# EntradaSensorTemperatura.net
KiCad netlist of a schematic drawn in Altium Designer
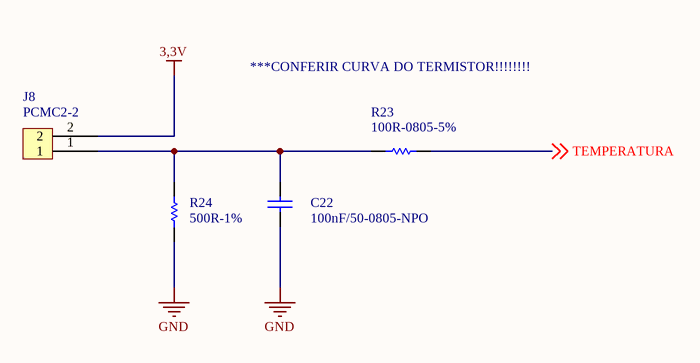
[diagram p0: EntradaSensorTemperatura.SchDoc]

(export (version "E")
  (design (tool "Eeschema 10.0.6"))
  (components
    (comp (ref "C22")
      (value "100nF/50-0805-NPO")
      (footprint "0805-REVISADO ONDA")
      (libsource (lib "AquinoLib") (part "100nF/50-0805-NPO"))
    )
    (comp (ref "J8") (value "PCMC2-2") (footprint "PCMC2-2") (libsource (lib "AquinoLib") (part "PCMC2-2")))
    (comp (ref "R23")
      (value "100R-0805-5%")
      (footprint "0805-REVISADO ONDA")
      (libsource (lib "AquinoLib") (part "100R-0805-5%"))
    )
    (comp (ref "R24")
      (value "500R-1%")
      (footprint "0805-REVISADO ONDA")
      (description "10K-0805-5%")
      (libsource (lib "AquinoLib") (part "10K-0805-5%"))
    )
  )
  (nets
    (net (code "1") (name "3,3V") (class "Default")
      (node (ref "J8") (pin "2") (pinfunction "2_2") (pintype "passive"))
    )
    (net (code "2") (name "GND") (class "Default")
      (node (ref "C22") (pin "1") (pinfunction "1_1") (pintype "passive"))
      (node (ref "R24") (pin "1") (pinfunction "1_1") (pintype "passive"))
    )
    (net (code "3") (name "Net-(C22-Pad2)") (class "Default")
      (node (ref "C22") (pin "2") (pinfunction "2_2") (pintype "passive"))
      (node (ref "J8") (pin "1") (pinfunction "1_1") (pintype "passive"))
      (node (ref "R23") (pin "1") (pinfunction "1_1") (pintype "passive"))
      (node (ref "R24") (pin "2") (pinfunction "2_2") (pintype "passive"))
    )
    (net (code "4") (name "TEMPERATURA") (class "Default")
      (node (ref "R23") (pin "2") (pinfunction "2_2") (pintype "passive"))
    )
  )
)
